# ST_LINK_V2-1.net
KiCad netlist of a schematic drawn in Altium Designer
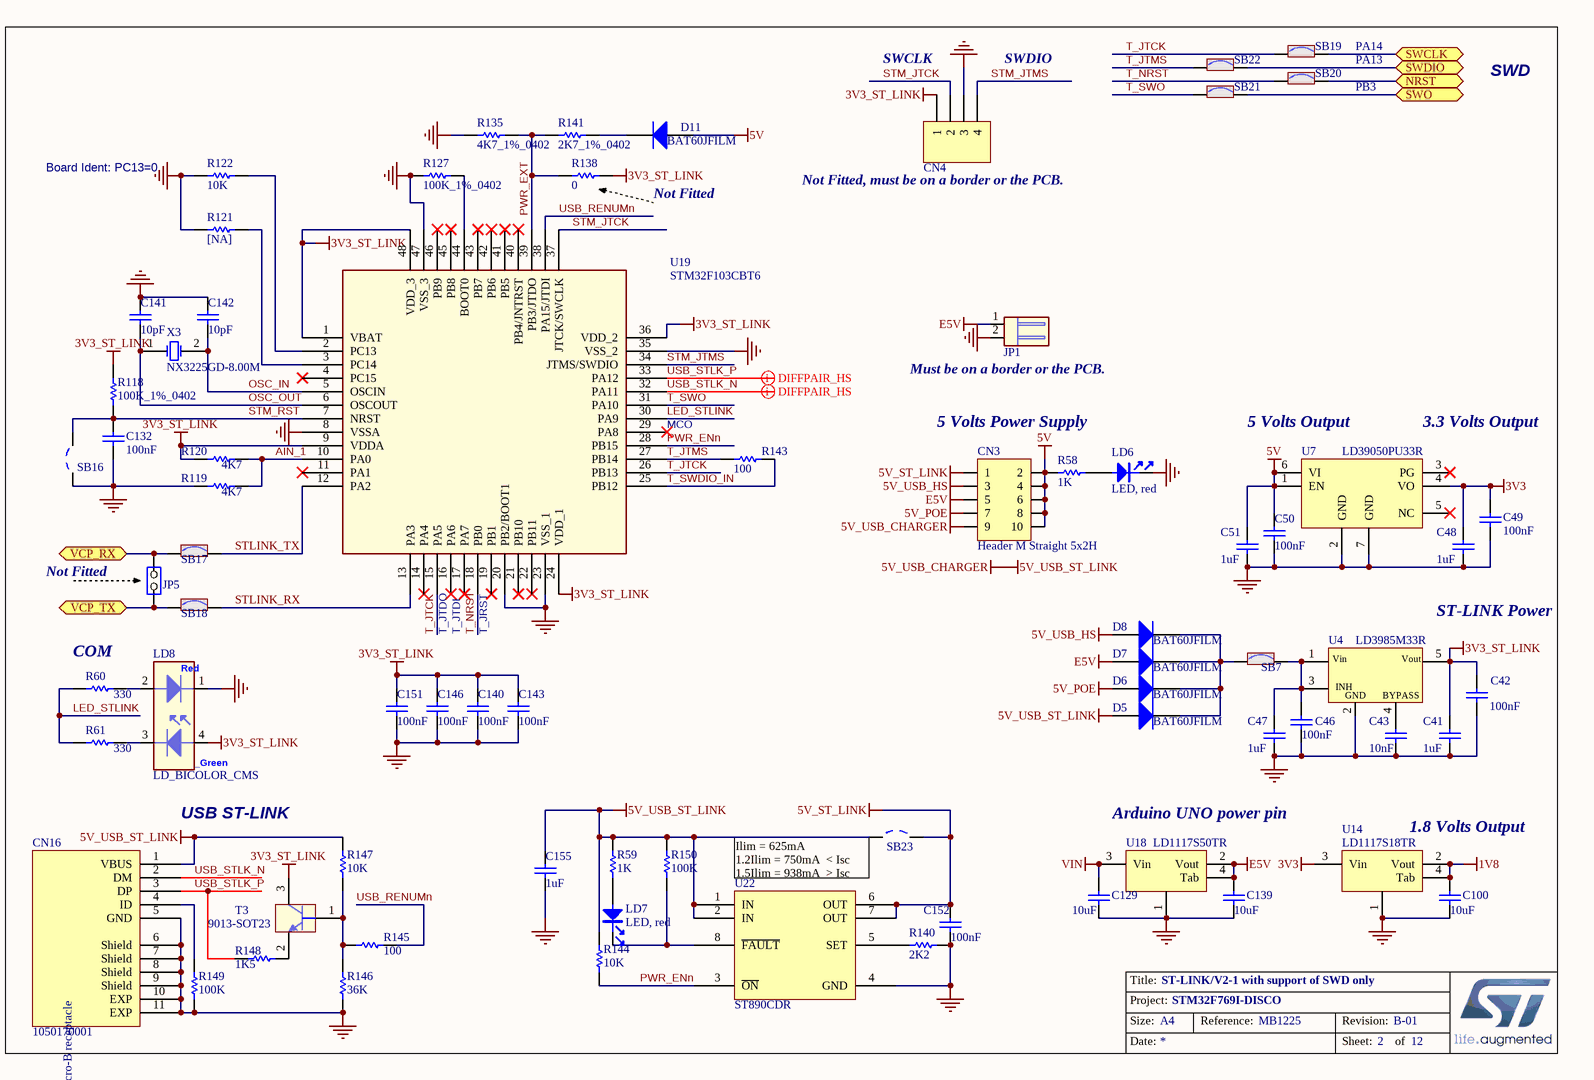
[diagram p0: ST_LINK_V2-1.SCHDOC]

(export (version "E")
  (design (tool "Eeschema 10.0.6"))
  (components
    (comp (ref "C41")
      (value "1uF")
      (footprint "0603C")
      (description "Capacitor,1uF,16V,X5R,10%,0603,YAGEO")
      (libsource (lib "MCD_TOOLS") (part "Cap_1uF_X5R_10%_0603"))
    )
    (comp (ref "C42")
      (value "100nF")
      (footprint "0402C")
      (description "Capacitor,100nF,16V,X7R,10%,0402,YAGEO")
      (libsource (lib "MCD_TOOLS") (part "Cap_100nF_X7R_10%_0402"))
    )
    (comp (ref "C43")
      (value "10nF")
      (footprint "0603C")
      (description "Capacitor,10nF,50V,X7R,10%,0603,YAGEO")
      (libsource (lib "MCD_TOOLS") (part "Cap_10nF_X7R_10%_0603"))
    )
    (comp (ref "C46")
      (value "100nF")
      (footprint "0402C")
      (description "Capacitor,100nF,16V,X7R,10%,0402,YAGEO")
      (libsource (lib "MCD_TOOLS") (part "Cap_100nF_X7R_10%_0402"))
    )
    (comp (ref "C47")
      (value "1uF")
      (footprint "0603C")
      (description "Capacitor,1uF,16V,X5R,10%,0603,YAGEO")
      (libsource (lib "MCD_TOOLS") (part "Cap_1uF_X5R_10%_0603"))
    )
    (comp (ref "C48")
      (value "1uF")
      (footprint "0603C")
      (description "Capacitor,1uF,16V,X5R,10%,0603,YAGEO")
      (libsource (lib "MCD_TOOLS") (part "Cap_1uF_X5R_10%_0603"))
    )
    (comp (ref "C49")
      (value "100nF")
      (footprint "0402C")
      (description "Capacitor,100nF,16V,X7R,10%,0402,YAGEO")
      (libsource (lib "MCD_TOOLS") (part "Cap_100nF_X7R_10%_0402"))
    )
    (comp (ref "C50")
      (value "100nF")
      (footprint "0402C")
      (description "Capacitor,100nF,16V,X7R,10%,0402,YAGEO")
      (libsource (lib "MCD_TOOLS") (part "Cap_100nF_X7R_10%_0402"))
    )
    (comp (ref "C51")
      (value "1uF")
      (footprint "0603C")
      (description "Capacitor,1uF,16V,X5R,10%,0603,YAGEO")
      (libsource (lib "MCD_TOOLS") (part "Cap_1uF_X5R_10%_0603"))
    )
    (comp (ref "C100")
      (value "10uF")
      (footprint "0603C")
      (description "Capacitor,10uF,6.3V,X5R,10%,0603,YAGEO")
      (libsource (lib "MCD_TOOLS") (part "Cap_10uF_X5R_10%_0603"))
    )
    (comp (ref "C129")
      (value "10uF")
      (footprint "0805C")
      (description "Capacitor,10uF,25V,X5R,10%,0805,YAGEO")
      (libsource (lib "MCD_TOOLS") (part "Cap_10uF_X5R_10%_0805"))
    )
    (comp (ref "C132")
      (value "100nF")
      (footprint "0402C")
      (description "Capacitor,100nF,16V,X7R,10%,0402,YAGEO")
      (libsource (lib "MCD_TOOLS") (part "Cap_100nF_X7R_10%_0402"))
    )
    (comp (ref "C139")
      (value "10uF")
      (footprint "0805C")
      (description "Capacitor,10uF,25V,X5R,10%,0805,YAGEO")
      (libsource (lib "MCD_TOOLS") (part "Cap_10uF_X5R_10%_0805"))
    )
    (comp (ref "C140")
      (value "100nF")
      (footprint "0402C")
      (description "Capacitor,100nF,16V,X7R,10%,0402,YAGEO")
      (libsource (lib "MCD_TOOLS") (part "Cap_100nF_X7R_10%_0402"))
    )
    (comp (ref "C141")
      (value "10pF")
      (footprint "0402C")
      (description "Capacitor,10pF,50V,NPO,5%,0402,YAGEO")
      (libsource (lib "MCD_TOOLS") (part "Cap_10pF_NPO_5%_0402"))
    )
    (comp (ref "C142")
      (value "10pF")
      (footprint "0402C")
      (description "Capacitor,10pF,50V,NPO,5%,0402,YAGEO")
      (libsource (lib "MCD_TOOLS") (part "Cap_10pF_NPO_5%_0402"))
    )
    (comp (ref "C143")
      (value "100nF")
      (footprint "0402C")
      (description "Capacitor,100nF,16V,X7R,10%,0402,YAGEO")
      (libsource (lib "MCD_TOOLS") (part "Cap_100nF_X7R_10%_0402"))
    )
    (comp (ref "C146")
      (value "100nF")
      (footprint "0402C")
      (description "Capacitor,100nF,16V,X7R,10%,0402,YAGEO")
      (libsource (lib "MCD_TOOLS") (part "Cap_100nF_X7R_10%_0402"))
    )
    (comp (ref "C151")
      (value "100nF")
      (footprint "0402C")
      (description "Capacitor,100nF,16V,X7R,10%,0402,YAGEO")
      (libsource (lib "MCD_TOOLS") (part "Cap_100nF_X7R_10%_0402"))
    )
    (comp (ref "C152")
      (value "100nF")
      (footprint "0402C")
      (description "Capacitor,100nF,16V,X7R,10%,0402,YAGEO")
      (libsource (lib "MCD_TOOLS") (part "Cap_100nF_X7R_10%_0402"))
    )
    (comp (ref "C155")
      (value "1uF")
      (footprint "0603C")
      (description "Capacitor,1uF,16V,X5R,10%,0603,YAGEO")
      (libsource (lib "MCD_TOOLS_CAPACITOR") (part "Cap_1uF_X5R_10%_0603"))
    )
    (comp (ref "CN3")
      (value "Header M Straight 5x2H")
      (footprint "HDR_2X5_2R54")
      (description "Header Male, 5-Pin, Dual row, Straight, AMD")
      (libsource (lib "MCD_TOOLS_CONNECTOR") (part "Header 5X2M"))
    )
    (comp (ref "CN4")
      (value "Header 4")
      (footprint "HDR_1X4_2R54")
      (description "Header, 4-Pin")
      (fields (field (name "PUBLISHER") "Altium Limited"))
      (libsource (lib "MCD_TOOLS_CONNECTOR") (part "Header 4"))
    )
    (comp (ref "CN16")
      (value "1050170001")
      (footprint "MICRO_USB_B_105017")
      (description "USB-MICRO-B, 1050170001, SMT, MOLEX")
      (libsource (lib "MCD_TOOLS_CONNECTOR") (part "1050170001"))
    )
    (comp (ref "D5")
      (value "BAT60JFILM")
      (footprint "SOD-323")
      (libsource (lib "MCD_TOOLS_MISCELLANEOUS") (part "BAT60JFILM"))
    )
    (comp (ref "D6")
      (value "BAT60JFILM")
      (footprint "SOD-323")
      (libsource (lib "MCD_TOOLS_MISCELLANEOUS") (part "BAT60JFILM"))
    )
    (comp (ref "D7")
      (value "BAT60JFILM")
      (footprint "SOD-323")
      (libsource (lib "MCD_TOOLS_MISCELLANEOUS") (part "BAT60JFILM"))
    )
    (comp (ref "D8")
      (value "BAT60JFILM")
      (footprint "SOD-323")
      (libsource (lib "MCD_TOOLS_MISCELLANEOUS") (part "BAT60JFILM"))
    )
    (comp (ref "D11")
      (value "BAT60JFILM")
      (footprint "SOD-323")
      (libsource (lib "MCD_TOOLS_MISCELLANEOUS") (part "BAT60JFILM"))
    )
    (comp (ref "JP1")
      (value "WF25402-06421")
      (footprint "HDR_1X2_2R54_RA_11R35")
      (description "Header, 2-Pins, Single row, Right Angle, 2.54 mm pitch, DIP")
      (libsource (lib "MCD_TOOLS_CONNECTOR") (part "JP2_RA"))
    )
    (comp (ref "JP5") (value "JP2") (footprint "SIP2") (libsource (lib "MCD_TOOLS_CONNECTOR") (part "JP2")))
    (comp (ref "LD6")
      (value "LED, red")
      (footprint "0603D")
      (description "LED,red,0603,19-213-R6C-AP1Q2B/3T,everlight")
      (libsource (lib "MCD_TOOLS") (part "LED_red"))
    )
    (comp (ref "LD7")
      (value "LED, red")
      (footprint "0603D")
      (description "LED,red,0603,19-213-R6C-AP1Q2B/3T,everlight")
      (libsource (lib "MCD_TOOLS") (part "LED_red"))
    )
    (comp (ref "LD8")
      (value "LD_BICOLOR_CMS")
      (footprint "LED2_3528")
      (description "Bicolor Led")
      (libsource (lib "MCD_TOOLS_MISCELLANEOUS") (part "LD_BICOLOR_CMS"))
    )
    (comp (ref "R58")
      (value "1K")
      (footprint "0402R")
      (description "Resistor,1K,0402,1%,YAGEO")
      (libsource (lib "MCD_TOOLS") (part "Res_1K_1%_0402"))
    )
    (comp (ref "R59")
      (value "1K")
      (footprint "0402R")
      (description "Resistor,1K,0402,1%,YAGEO")
      (libsource (lib "MCD_TOOLS") (part "Res_1K_1%_0402"))
    )
    (comp (ref "R60")
      (value "330")
      (footprint "0402R")
      (description "Resistor,330,0402,1%,YAGEO")
      (libsource (lib "MCD_TOOLS") (part "Res_330_1%_0402"))
    )
    (comp (ref "R61")
      (value "330")
      (footprint "0402R")
      (description "Resistor,330,0402,1%,YAGEO")
      (libsource (lib "MCD_TOOLS") (part "Res_330_1%_0402"))
    )
    (comp (ref "R118")
      (value "100K_1%_0402")
      (footprint "0402R")
      (description "Resistor,100K,0402,1%,YAGEO")
      (libsource (lib "MCD_TOOLS_RESISTOR") (part "Res_100K_1%_0402"))
    )
    (comp (ref "R119")
      (value "4K7")
      (footprint "0402R")
      (description "Resistor,4K7,0402,1%,YAGEO")
      (libsource (lib "MCD_TOOLS_RESISTOR") (part "Res_4K7_1%_0402"))
    )
    (comp (ref "R120")
      (value "4K7")
      (footprint "0402R")
      (description "Resistor,4K7,0402,1%,YAGEO")
      (libsource (lib "MCD_TOOLS_RESISTOR") (part "Res_4K7_1%_0402"))
    )
    (comp (ref "R121")
      (value "[NA]")
      (footprint "0402R")
      (description "Resistor,[NA],0402")
      (libsource (lib "MCD_TOOLS") (part "Res_NA_0402"))
    )
    (comp (ref "R122")
      (value "10K")
      (footprint "0402R")
      (description "Resistor,10K,0402,1%,YAGEO")
      (libsource (lib "MCD_TOOLS") (part "Res_10K_1%_0402"))
    )
    (comp (ref "R127")
      (value "100K_1%_0402")
      (footprint "0402R")
      (description "Resistor,100K,0402,1%,YAGEO")
      (libsource (lib "MCD_TOOLS_RESISTOR") (part "Res_100K_1%_0402"))
    )
    (comp (ref "R135")
      (value "4K7_1%_0402")
      (footprint "0402R")
      (description "Resistor,4K7,0402,1%,YAGEO")
      (libsource (lib "MCD_TOOLS_RESISTOR") (part "Res_4K7_1%_0402"))
    )
    (comp (ref "R138")
      (value "0")
      (footprint "0402R")
      (description "Resistor,0,0402,5%,YAGEO")
      (libsource (lib "MCD_TOOLS") (part "Res_0_5%_0402"))
    )
    (comp (ref "R140")
      (value "2K2")
      (footprint "0402R")
      (description "Resistor,2K2,0402,1%,YAGEO")
      (libsource (lib "MCD_TOOLS_RESISTOR") (part "Res_2K2_1%_0402"))
    )
    (comp (ref "R141")
      (value "2K7_1%_0402")
      (footprint "0402R")
      (description "Resistor,2K7,0402,1%,YAGEO")
      (libsource (lib "MCD_TOOLS_RESISTOR") (part "Res_2K7_1%_0402"))
    )
    (comp (ref "R143")
      (value "100")
      (footprint "0402R")
      (description "Resistor,100,0402,1%,YAGEO")
      (libsource (lib "MCD_TOOLS") (part "Res_100_1%_0402"))
    )
    (comp (ref "R144")
      (value "10K")
      (footprint "0402R")
      (description "Resistor,10K,0402,1%,YAGEO")
      (libsource (lib "MCD_TOOLS") (part "Res_10K_1%_0402"))
    )
    (comp (ref "R145")
      (value "100")
      (footprint "0402R")
      (description "Resistor,100,0402,1%,YAGEO")
      (libsource (lib "MCD_TOOLS") (part "Res_100_1%_0402"))
    )
    (comp (ref "R146")
      (value "36K")
      (footprint "0402R")
      (description "Resistor,36K,0402,1%,YAGEO")
      (libsource (lib "MCD_TOOLS") (part "Res_36K_1%_0402"))
    )
    (comp (ref "R147")
      (value "10K")
      (footprint "0402R")
      (description "Resistor,10K,0402,1%,YAGEO")
      (libsource (lib "MCD_TOOLS") (part "Res_10K_1%_0402"))
    )
    (comp (ref "R148")
      (value "1K5")
      (footprint "0402R")
      (description "Resistor,1K5,0402,1%,YAGEO")
      (libsource (lib "MCD_TOOLS") (part "Res_1K5_1%_0402"))
    )
    (comp (ref "R149")
      (value "100K")
      (footprint "0402R")
      (description "Resistor,100K,0402,1%,YAGEO")
      (libsource (lib "MCD_TOOLS_RESISTOR") (part "Res_100K_1%_0402"))
    )
    (comp (ref "R150")
      (value "100K")
      (footprint "0402R")
      (description "Resistor,100K,0402,1%,YAGEO")
      (libsource (lib "MCD_TOOLS_RESISTOR") (part "Res_100K_1%_0402"))
    )
    (comp (ref "SB7")
      (value "Solder Bridge ON")
      (footprint "JP2_SMD")
      (libsource (lib "MCD_TOOLS") (part "SB_ON"))
    )
    (comp (ref "SB16")
      (value "Solder Bridge OFF")
      (footprint "JP2_SMD")
      (libsource (lib "MCD_TOOLS") (part "SB_OFF"))
    )
    (comp (ref "SB17")
      (value "Solder Bridge ON")
      (footprint "JP2_SMD")
      (libsource (lib "MCD_TOOLS") (part "SB_ON"))
    )
    (comp (ref "SB18")
      (value "Solder Bridge ON")
      (footprint "JP2_SMD")
      (libsource (lib "MCD_TOOLS") (part "SB_ON"))
    )
    (comp (ref "SB19")
      (value "Solder Bridge ON")
      (footprint "JP2_SMD")
      (libsource (lib "MCD_TOOLS") (part "SB_ON"))
    )
    (comp (ref "SB20")
      (value "Solder Bridge ON")
      (footprint "JP2_SMD")
      (libsource (lib "MCD_TOOLS") (part "SB_ON"))
    )
    (comp (ref "SB21")
      (value "Solder Bridge ON")
      (footprint "JP2_SMD")
      (libsource (lib "MCD_TOOLS") (part "SB_ON"))
    )
    (comp (ref "SB22")
      (value "Solder Bridge ON")
      (footprint "JP2_SMD")
      (libsource (lib "MCD_TOOLS") (part "SB_ON"))
    )
    (comp (ref "SB23")
      (value "Solder Bridge OFF")
      (footprint "JP2_SMD")
      (libsource (lib "MCD_TOOLS") (part "SB_OFF"))
    )
    (comp (ref "T3")
      (value "9013-SOT23")
      (footprint "SOT-23")
      (description "NPN Bipolar Transistor, SOT-23 Footprint")
      (libsource (lib "MCD_TOOLS_MISCELLANEOUS") (part "9013-SOT23"))
    )
    (comp (ref "U4")
      (value "LD3985M33R")
      (footprint "SOT-23-5L")
      (description "Ultra low drop-low noise BiCMOS voltage, regulators low ESR capacitors compatible")
      (libsource (lib "MCD_TOOLS_MISCELLANEOUS") (part "LD3985M33R"))
    )
    (comp (ref "U7")
      (value "LD39050PU33R")
      (footprint "DFN6_0R95_3X3")
      (description "Ultra low drop-low , 500 mA low quiescent current")
      (libsource (lib "MCD_TOOLS_MISCELLANEOUS") (part "LD39050P"))
    )
    (comp (ref "U14")
      (value "LD1117S18TR")
      (footprint "SOT-223")
      (description "LOW DROP FIXED AND ADJUSTABLE POSITIVE VOLTAGE REGULATORS (1.8 Volts)")
      (libsource (lib "MCD_TOOLS") (part "LD1117S18TR"))
    )
    (comp (ref "U18")
      (value "LD1117S50TR")
      (footprint "SOT-223")
      (description "IC REG LDO 5V 0.8A SOT223")
      (libsource (lib "MCD_TOOLS") (part "LD1117S50TR"))
    )
    (comp (ref "U19")
      (value "STM32F103CBT6")
      (footprint "LQFP48_0R5_9X9")
      (description "Medium-density performance line ARM-based 32-bit MCU with 128KB Flash")
      (libsource (lib "MCD_TOOLS_MCU") (part "STM32F103CBT6"))
    )
    (comp (ref "U22")
      (value "ST890CDR")
      (footprint "SOIC8_1R27_4R9X6")
      (description "1.2 A current limited high-side power switch with thermal shutdown")
      (libsource (lib "MCD_TOOLS_MISCELLANEOUS") (part "ST890CDR"))
    )
    (comp (ref "X3")
      (value "NX3225GD-8.00M")
      (footprint "XTAL_2SM_3R2X2R5_H1")
      (description "Crystal 8Mhz, 8pF, -+50PPM, SMD")
      (libsource (lib "MCD_TOOLS_MISCELLANEOUS") (part "XTAL_8M_NX3225GD"))
    )
  )
  (nets
    (net (code "1") (name "/AIN_1") (class "Default")
      (node (ref "R119") (pin "2") (pinfunction "2_2") (pintype "passive"))
      (node (ref "R120") (pin "2") (pinfunction "2_2") (pintype "passive"))
      (node (ref "U19") (pin "10") (pinfunction "PA0_10") (pintype "passive"))
    )
    (net (code "2") (name "/LED_STLINK") (class "Default")
      (node (ref "R60") (pin "1") (pinfunction "1_1") (pintype "passive"))
      (node (ref "R61") (pin "1") (pinfunction "1_1") (pintype "passive"))
      (node (ref "U19") (pin "30") (pinfunction "PA9_30") (pintype "passive"))
    )
    (net (code "3") (name "/NRST") (class "Default")
      (node (ref "SB20") (pin "2") (pinfunction "2_2") (pintype "passive"))
    )
    (net (code "4") (name "/OSC_IN") (class "Default")
      (node (ref "C142") (pin "2") (pinfunction "2_2") (pintype "passive"))
      (node (ref "U19") (pin "5") (pinfunction "OSCIN_5") (pintype "passive"))
      (node (ref "X3") (pin "2") (pinfunction "OSC2_2") (pintype "passive"))
    )
    (net (code "5") (name "/OSC_OUT") (class "Default")
      (node (ref "C141") (pin "2") (pinfunction "2_2") (pintype "passive"))
      (node (ref "U19") (pin "6") (pinfunction "OSCOUT_6") (pintype "passive"))
      (node (ref "X3") (pin "1") (pinfunction "OSC1_1") (pintype "passive"))
    )
    (net (code "6") (name "/PWR_ENn") (class "Default")
      (node (ref "R144") (pin "1") (pinfunction "1_1") (pintype "passive"))
      (node (ref "U19") (pin "28") (pinfunction "PB15_28") (pintype "passive"))
      (node (ref "U22") (pin "3") (pinfunction "~{ON}_3") (pintype "passive"))
    )
    (net (code "7") (name "/PWR_EXT") (class "Default")
      (node (ref "R135") (pin "2") (pinfunction "2_2") (pintype "passive"))
      (node (ref "R138") (pin "1") (pinfunction "1_1") (pintype "passive"))
      (node (ref "R141") (pin "1") (pinfunction "1_1") (pintype "passive"))
      (node (ref "U19") (pin "39") (pinfunction "PB3/JTDO_39") (pintype "passive"))
    )
    (net (code "8") (name "/STLINK_RX") (class "Default")
      (node (ref "SB18") (pin "2") (pinfunction "2_2") (pintype "passive"))
      (node (ref "U19") (pin "13") (pinfunction "PA3_13") (pintype "passive"))
    )
    (net (code "9") (name "/STLINK_TX") (class "Default")
      (node (ref "SB17") (pin "2") (pinfunction "2_2") (pintype "passive"))
      (node (ref "U19") (pin "12") (pinfunction "PA2_12") (pintype "passive"))
    )
    (net (code "10") (name "/STM_JTCK") (class "Default")
      (node (ref "CN4") (pin "2") (pinfunction "2_2") (pintype "passive"))
      (node (ref "U19") (pin "37") (pinfunction "JTCK/SWCLK_37") (pintype "passive"))
    )
    (net (code "11") (name "/STM_JTMS") (class "Default")
      (node (ref "CN4") (pin "4") (pinfunction "4_4") (pintype "passive"))
      (node (ref "U19") (pin "34") (pinfunction "JTMS/SWDIO_34") (pintype "passive"))
    )
    (net (code "12") (name "/STM_RST") (class "Default")
      (node (ref "C132") (pin "2") (pinfunction "2_2") (pintype "passive"))
      (node (ref "R118") (pin "1") (pinfunction "1_1") (pintype "passive"))
      (node (ref "SB16") (pin "2") (pinfunction "2_2") (pintype "passive"))
      (node (ref "U19") (pin "7") (pinfunction "NRST_7") (pintype "passive"))
    )
    (net (code "13") (name "/SWCLK") (class "Default")
      (node (ref "SB19") (pin "2") (pinfunction "2_2") (pintype "passive"))
    )
    (net (code "14") (name "/SWDIO") (class "Default")
      (node (ref "SB22") (pin "2") (pinfunction "2_2") (pintype "passive"))
    )
    (net (code "15") (name "/SWO") (class "Default")
      (node (ref "SB21") (pin "2") (pinfunction "2_2") (pintype "passive"))
    )
    (net (code "16") (name "/T_JTCK") (class "Default")
      (node (ref "SB19") (pin "1") (pinfunction "1_1") (pintype "passive"))
      (node (ref "U19") (pin "15") (pinfunction "PA5_15") (pintype "passive"))
      (node (ref "U19") (pin "26") (pinfunction "PB13_26") (pintype "passive"))
    )
    (net (code "17") (name "/T_JTMS") (class "Default")
      (node (ref "R143") (pin "1") (pinfunction "1_1") (pintype "passive"))
      (node (ref "SB22") (pin "1") (pinfunction "1_1") (pintype "passive"))
      (node (ref "U19") (pin "27") (pinfunction "PB14_27") (pintype "passive"))
    )
    (net (code "18") (name "/T_NRST") (class "Default")
      (node (ref "SB20") (pin "1") (pinfunction "1_1") (pintype "passive"))
      (node (ref "U19") (pin "18") (pinfunction "PB0_18") (pintype "passive"))
    )
    (net (code "19") (name "/T_SWDIO_IN") (class "Default")
      (node (ref "R143") (pin "2") (pinfunction "2_2") (pintype "passive"))
      (node (ref "U19") (pin "25") (pinfunction "PB12_25") (pintype "passive"))
    )
    (net (code "20") (name "/T_SWO") (class "Default")
      (node (ref "SB21") (pin "1") (pinfunction "1_1") (pintype "passive"))
      (node (ref "U19") (pin "31") (pinfunction "PA10_31") (pintype "passive"))
    )
    (net (code "21") (name "/USB_RENUMn") (class "Default")
      (node (ref "R145") (pin "2") (pinfunction "2_2") (pintype "passive"))
      (node (ref "U19") (pin "38") (pinfunction "PA15/JTDI_38") (pintype "passive"))
    )
    (net (code "22") (name "/USB_STLK_N") (class "Default")
      (node (ref "CN16") (pin "2") (pinfunction "DM_2") (pintype "passive"))
      (node (ref "U19") (pin "32") (pinfunction "PA11_32") (pintype "passive"))
    )
    (net (code "23") (name "/USB_STLK_P") (class "Default")
      (node (ref "CN16") (pin "3") (pinfunction "DP_3") (pintype "passive"))
      (node (ref "R148") (pin "1") (pinfunction "1_1") (pintype "passive"))
      (node (ref "U19") (pin "33") (pinfunction "PA12_33") (pintype "passive"))
    )
    (net (code "24") (name "/VCP_RX") (class "Default")
      (node (ref "JP5") (pin "2") (pinfunction "NO_2") (pintype "passive"))
      (node (ref "SB17") (pin "1") (pinfunction "1_1") (pintype "passive"))
    )
    (net (code "25") (name "/VCP_TX") (class "Default")
      (node (ref "JP5") (pin "1") (pinfunction "COMMON_1") (pintype "passive"))
      (node (ref "SB18") (pin "1") (pinfunction "1_1") (pintype "passive"))
    )
    (net (code "26") (name "1V8") (class "Default")
      (node (ref "C100") (pin "2") (pinfunction "2_2") (pintype "passive"))
      (node (ref "U14") (pin "2") (pinfunction "Vout_2") (pintype "passive"))
      (node (ref "U14") (pin "4") (pinfunction "Tab_4") (pintype "passive"))
    )
    (net (code "27") (name "3V3") (class "Default")
      (node (ref "C48") (pin "2") (pinfunction "2_2") (pintype "passive"))
      (node (ref "C49") (pin "2") (pinfunction "2_2") (pintype "passive"))
      (node (ref "U14") (pin "3") (pinfunction "Vin_3") (pintype "passive"))
      (node (ref "U7") (pin "4") (pinfunction "VO_4") (pintype "passive"))
    )
    (net (code "28") (name "3V3_ST_LINK") (class "Default")
      (node (ref "C140") (pin "1") (pinfunction "1_1") (pintype "passive"))
      (node (ref "C143") (pin "2") (pinfunction "2_2") (pintype "passive"))
      (node (ref "C146") (pin "2") (pinfunction "2_2") (pintype "passive"))
      (node (ref "C151") (pin "2") (pinfunction "2_2") (pintype "passive"))
      (node (ref "C41") (pin "1") (pinfunction "1_1") (pintype "passive"))
      (node (ref "C42") (pin "2") (pinfunction "2_2") (pintype "passive"))
      (node (ref "CN4") (pin "1") (pinfunction "1_1") (pintype "passive"))
      (node (ref "LD8") (pin "4") (pinfunction "4_4") (pintype "passive"))
      (node (ref "R118") (pin "2") (pinfunction "2_2") (pintype "passive"))
      (node (ref "R120") (pin "1") (pinfunction "1_1") (pintype "passive"))
      (node (ref "R138") (pin "2") (pinfunction "2_2") (pintype "passive"))
      (node (ref "T3") (pin "3") (pinfunction "C_3") (pintype "passive"))
      (node (ref "U19") (pin "1") (pinfunction "VBAT_1") (pintype "passive"))
      (node (ref "U19") (pin "24") (pinfunction "VDD_1_24") (pintype "passive"))
      (node (ref "U19") (pin "36") (pinfunction "VDD_2_36") (pintype "passive"))
      (node (ref "U19") (pin "48") (pinfunction "VDD_3_48") (pintype "passive"))
      (node (ref "U19") (pin "9") (pinfunction "VDDA_9") (pintype "passive"))
      (node (ref "U4") (pin "5") (pinfunction "Vout_5") (pintype "passive"))
    )
    (net (code "29") (name "5V") (class "Default")
      (node (ref "C50") (pin "2") (pinfunction "2_2") (pintype "passive"))
      (node (ref "C51") (pin "2") (pinfunction "2_2") (pintype "passive"))
      (node (ref "CN3") (pin "10") (pinfunction "10_10") (pintype "passive"))
      (node (ref "CN3") (pin "2") (pinfunction "2_2") (pintype "passive"))
      (node (ref "CN3") (pin "4") (pinfunction "4_4") (pintype "passive"))
      (node (ref "CN3") (pin "6") (pinfunction "6_6") (pintype "passive"))
      (node (ref "CN3") (pin "8") (pinfunction "8_8") (pintype "passive"))
      (node (ref "D11") (pin "1") (pinfunction "A_1") (pintype "passive"))
      (node (ref "R58") (pin "1") (pinfunction "1_1") (pintype "passive"))
      (node (ref "U7") (pin "1") (pinfunction "EN_1") (pintype "passive"))
      (node (ref "U7") (pin "6") (pinfunction "VI_6") (pintype "passive"))
    )
    (net (code "30") (name "5V_POE") (class "Default")
      (node (ref "CN3") (pin "7") (pinfunction "7_7") (pintype "passive"))
      (node (ref "D6") (pin "1") (pinfunction "A_1") (pintype "passive"))
    )
    (net (code "31") (name "5V_ST_LINK") (class "Default")
      (node (ref "C152") (pin "2") (pinfunction "2_2") (pintype "passive"))
      (node (ref "CN3") (pin "1") (pinfunction "1_1") (pintype "passive"))
      (node (ref "SB23") (pin "2") (pinfunction "2_2") (pintype "passive"))
      (node (ref "U22") (pin "6") (pinfunction "OUT_6") (pintype "passive"))
      (node (ref "U22") (pin "7") (pinfunction "OUT_7") (pintype "passive"))
    )
    (net (code "32") (name "5V_USB_CHARGER") (class "Default")
      (node (ref "C155") (pin "2") (pinfunction "2_2") (pintype "passive"))
      (node (ref "CN16") (pin "1") (pinfunction "VBUS_1") (pintype "passive"))
      (node (ref "CN3") (pin "9") (pinfunction "9_9") (pintype "passive"))
      (node (ref "D5") (pin "1") (pinfunction "A_1") (pintype "passive"))
      (node (ref "R144") (pin "2") (pinfunction "2_2") (pintype "passive"))
      (node (ref "R147") (pin "2") (pinfunction "2_2") (pintype "passive"))
      (node (ref "R150") (pin "2") (pinfunction "2_2") (pintype "passive"))
      (node (ref "R59") (pin "2") (pinfunction "2_2") (pintype "passive"))
      (node (ref "SB23") (pin "1") (pinfunction "1_1") (pintype "passive"))
      (node (ref "U22") (pin "1") (pinfunction "IN_1") (pintype "passive"))
      (node (ref "U22") (pin "2") (pinfunction "IN_2") (pintype "passive"))
    )
    (net (code "33") (name "5V_USB_HS") (class "Default")
      (node (ref "CN3") (pin "3") (pinfunction "3_3") (pintype "passive"))
      (node (ref "D8") (pin "1") (pinfunction "A_1") (pintype "passive"))
    )
    (net (code "34") (name "E5V") (class "Default")
      (node (ref "C139") (pin "2") (pinfunction "2_2") (pintype "passive"))
      (node (ref "CN3") (pin "5") (pinfunction "5_5") (pintype "passive"))
      (node (ref "D7") (pin "1") (pinfunction "A_1") (pintype "passive"))
      (node (ref "JP1") (pin "1") (pinfunction "1_1") (pintype "passive"))
      (node (ref "U18") (pin "2") (pinfunction "Vout_2") (pintype "passive"))
      (node (ref "U18") (pin "4") (pinfunction "Tab_4") (pintype "passive"))
    )
    (net (code "35") (name "GND") (class "Default")
      (node (ref "C100") (pin "1") (pinfunction "1_1") (pintype "passive"))
      (node (ref "C129") (pin "1") (pinfunction "1_1") (pintype "passive"))
      (node (ref "C132") (pin "1") (pinfunction "1_1") (pintype "passive"))
      (node (ref "C139") (pin "1") (pinfunction "1_1") (pintype "passive"))
      (node (ref "C140") (pin "2") (pinfunction "2_2") (pintype "passive"))
      (node (ref "C141") (pin "1") (pinfunction "1_1") (pintype "passive"))
      (node (ref "C142") (pin "1") (pinfunction "1_1") (pintype "passive"))
      (node (ref "C143") (pin "1") (pinfunction "1_1") (pintype "passive"))
      (node (ref "C146") (pin "1") (pinfunction "1_1") (pintype "passive"))
      (node (ref "C151") (pin "1") (pinfunction "1_1") (pintype "passive"))
      (node (ref "C152") (pin "1") (pinfunction "1_1") (pintype "passive"))
      (node (ref "C155") (pin "1") (pinfunction "1_1") (pintype "passive"))
      (node (ref "C41") (pin "2") (pinfunction "2_2") (pintype "passive"))
      (node (ref "C42") (pin "1") (pinfunction "1_1") (pintype "passive"))
      (node (ref "C43") (pin "1") (pinfunction "1_1") (pintype "passive"))
      (node (ref "C46") (pin "1") (pinfunction "1_1") (pintype "passive"))
      (node (ref "C47") (pin "1") (pinfunction "1_1") (pintype "passive"))
      (node (ref "C48") (pin "1") (pinfunction "1_1") (pintype "passive"))
      (node (ref "C49") (pin "1") (pinfunction "1_1") (pintype "passive"))
      (node (ref "C50") (pin "1") (pinfunction "1_1") (pintype "passive"))
      (node (ref "C51") (pin "1") (pinfunction "1_1") (pintype "passive"))
      (node (ref "CN16") (pin "10") (pinfunction "EXP_10") (pintype "passive"))
      (node (ref "CN16") (pin "11") (pinfunction "EXP_11") (pintype "passive"))
      (node (ref "CN16") (pin "5") (pinfunction "GND_5") (pintype "passive"))
      (node (ref "CN16") (pin "6") (pinfunction "Shield_6") (pintype "passive"))
      (node (ref "CN16") (pin "7") (pinfunction "Shield_7") (pintype "passive"))
      (node (ref "CN16") (pin "8") (pinfunction "Shield_8") (pintype "passive"))
      (node (ref "CN16") (pin "9") (pinfunction "Shield_9") (pintype "passive"))
      (node (ref "CN4") (pin "3") (pinfunction "3_3") (pintype "passive"))
      (node (ref "JP1") (pin "2") (pinfunction "2_2") (pintype "passive"))
      (node (ref "LD6") (pin "2") (pintype "passive"))
      (node (ref "LD8") (pin "1") (pinfunction "1_1") (pintype "passive"))
      (node (ref "R119") (pin "1") (pinfunction "1_1") (pintype "passive"))
      (node (ref "R121") (pin "1") (pinfunction "1_1") (pintype "passive"))
      (node (ref "R122") (pin "1") (pinfunction "1_1") (pintype "passive"))
      (node (ref "R127") (pin "1") (pinfunction "1_1") (pintype "passive"))
      (node (ref "R135") (pin "1") (pinfunction "1_1") (pintype "passive"))
      (node (ref "R140") (pin "2") (pinfunction "2_2") (pintype "passive"))
      (node (ref "R146") (pin "1") (pinfunction "1_1") (pintype "passive"))
      (node (ref "R149") (pin "1") (pinfunction "1_1") (pintype "passive"))
      (node (ref "SB16") (pin "1") (pinfunction "1_1") (pintype "passive"))
      (node (ref "U14") (pin "1") (pintype "passive"))
      (node (ref "U18") (pin "1") (pintype "passive"))
      (node (ref "U19") (pin "20") (pinfunction "PB2/BOOT1_20") (pintype "passive"))
      (node (ref "U19") (pin "23") (pinfunction "VSS_1_23") (pintype "passive"))
      (node (ref "U19") (pin "35") (pinfunction "VSS_2_35") (pintype "passive"))
      (node (ref "U19") (pin "47") (pinfunction "VSS_3_47") (pintype "passive"))
      (node (ref "U19") (pin "8") (pinfunction "VSSA_8") (pintype "passive"))
      (node (ref "U22") (pin "4") (pinfunction "GND_4") (pintype "passive"))
      (node (ref "U4") (pin "2") (pinfunction "GND_2") (pintype "passive"))
      (node (ref "U7") (pin "2") (pinfunction "GND_2") (pintype "passive"))
      (node (ref "U7") (pin "7") (pinfunction "GND_7") (pintype "passive"))
    )
    (net (code "36") (name "Net-(CN16-ID)") (class "Default")
      (node (ref "CN16") (pin "4") (pinfunction "ID_4") (pintype "passive"))
      (node (ref "R149") (pin "2") (pinfunction "2_2") (pintype "passive"))
    )
    (net (code "37") (name "Net-(D5-K)") (class "Default")
      (node (ref "D5") (pin "2") (pinfunction "K_2") (pintype "passive"))
      (node (ref "D6") (pin "2") (pinfunction "K_2") (pintype "passive"))
      (node (ref "D7") (pin "2") (pinfunction "K_2") (pintype "passive"))
      (node (ref "D8") (pin "2") (pinfunction "K_2") (pintype "passive"))
      (node (ref "SB7") (pin "1") (pinfunction "1_1") (pintype "passive"))
    )
    (net (code "38") (name "Net-(D11-K)") (class "Default")
      (node (ref "D11") (pin "2") (pinfunction "K_2") (pintype "passive"))
      (node (ref "R141") (pin "2") (pinfunction "2_2") (pintype "passive"))
    )
    (net (code "39") (name "Net-(LD6-Pad1)") (class "Default")
      (node (ref "LD6") (pin "1") (pintype "passive"))
      (node (ref "R58") (pin "2") (pinfunction "2_2") (pintype "passive"))
    )
    (net (code "40") (name "Net-(LD7-Pad1)") (class "Default")
      (node (ref "LD7") (pin "1") (pintype "passive"))
      (node (ref "R59") (pin "1") (pinfunction "1_1") (pintype "passive"))
    )
    (net (code "41") (name "Net-(LD8-Pad2)") (class "Default")
      (node (ref "LD8") (pin "2") (pinfunction "2_2") (pintype "passive"))
      (node (ref "R60") (pin "2") (pinfunction "2_2") (pintype "passive"))
    )
    (net (code "42") (name "Net-(LD8-Pad3)") (class "Default")
      (node (ref "LD8") (pin "3") (pinfunction "3_3") (pintype "passive"))
      (node (ref "R61") (pin "2") (pinfunction "2_2") (pintype "passive"))
    )
    (net (code "43") (name "Net-(T3-B)") (class "Default")
      (node (ref "R145") (pin "1") (pinfunction "1_1") (pintype "passive"))
      (node (ref "R146") (pin "2") (pinfunction "2_2") (pintype "passive"))
      (node (ref "R147") (pin "1") (pinfunction "1_1") (pintype "passive"))
      (node (ref "T3") (pin "1") (pinfunction "B_1") (pintype "passive"))
    )
    (net (code "44") (name "Net-(T3-E)") (class "Default")
      (node (ref "R148") (pin "2") (pinfunction "2_2") (pintype "passive"))
      (node (ref "T3") (pin "2") (pinfunction "E_2") (pintype "passive"))
    )
    (net (code "45") (name "Net-(U4-BYPASS)") (class "Default")
      (node (ref "C43") (pin "2") (pinfunction "2_2") (pintype "passive"))
      (node (ref "U4") (pin "4") (pinfunction "BYPASS_4") (pintype "passive"))
    )
    (net (code "46") (name "Net-(U4-CE)") (class "Default")
      (node (ref "C46") (pin "2") (pinfunction "2_2") (pintype "passive"))
      (node (ref "C47") (pin "2") (pinfunction "2_2") (pintype "passive"))
      (node (ref "SB7") (pin "2") (pinfunction "2_2") (pintype "passive"))
      (node (ref "U4") (pin "1") (pinfunction "Vin_1") (pintype "passive"))
      (node (ref "U4") (pin "3") (pinfunction "CE_3") (pintype "passive"))
    )
    (net (code "47") (name "Net-(U19-BOOT0)") (class "Default")
      (node (ref "R127") (pin "2") (pinfunction "2_2") (pintype "passive"))
      (node (ref "U19") (pin "44") (pinfunction "BOOT0_44") (pintype "passive"))
    )
    (net (code "48") (name "Net-(U19-PC13)") (class "Default")
      (node (ref "R122") (pin "2") (pinfunction "2_2") (pintype "passive"))
      (node (ref "U19") (pin "2") (pinfunction "PC13_2") (pintype "passive"))
    )
    (net (code "49") (name "Net-(U19-PC14)") (class "Default")
      (node (ref "R121") (pin "2") (pinfunction "2_2") (pintype "passive"))
      (node (ref "U19") (pin "3") (pinfunction "PC14_3") (pintype "passive"))
    )
    (net (code "50") (name "Net-(U22-SET)") (class "Default")
      (node (ref "R140") (pin "1") (pinfunction "1_1") (pintype "passive"))
      (node (ref "U22") (pin "5") (pinfunction "SET_5") (pintype "passive"))
    )
    (net (code "51") (name "Net-(U22-~{FAULT})") (class "Default")
      (node (ref "LD7") (pin "2") (pintype "passive"))
      (node (ref "R150") (pin "1") (pinfunction "1_1") (pintype "passive"))
      (node (ref "U22") (pin "8") (pinfunction "~{FAULT}_8") (pintype "passive"))
    )
    (net (code "52") (name "VIN") (class "Default")
      (node (ref "C129") (pin "2") (pinfunction "2_2") (pintype "passive"))
      (node (ref "U18") (pin "3") (pinfunction "Vin_3") (pintype "passive"))
    )
    (net (code "53") (name "unconnected-(U7-NC-Pad5)") (class "Default")
      (node (ref "U7") (pin "5") (pinfunction "NC_5") (pintype "passive+no_connect"))
    )
    (net (code "54") (name "unconnected-(U7-PG-Pad3)") (class "Default")
      (node (ref "U7") (pin "3") (pinfunction "PG_3") (pintype "passive+no_connect"))
    )
    (net (code "55") (name "unconnected-(U19-PA1-Pad11)") (class "Default")
      (node (ref "U19") (pin "11") (pinfunction "PA1_11") (pintype "passive+no_connect"))
    )
    (net (code "56") (name "unconnected-(U19-PA4-Pad14)") (class "Default")
      (node (ref "U19") (pin "14") (pinfunction "PA4_14") (pintype "passive+no_connect"))
    )
    (net (code "57") (name "unconnected-(U19-PA6-Pad16)") (class "Default")
      (node (ref "U19") (pin "16") (pinfunction "PA6_16") (pintype "passive+no_connect"))
    )
    (net (code "58") (name "unconnected-(U19-PA7-Pad17)") (class "Default")
      (node (ref "U19") (pin "17") (pinfunction "PA7_17") (pintype "passive+no_connect"))
    )
    (net (code "59") (name "unconnected-(U19-PA8-Pad29)") (class "Default")
      (node (ref "U19") (pin "29") (pinfunction "PA8_29") (pintype "passive+no_connect"))
    )
    (net (code "60") (name "unconnected-(U19-PB1-Pad19)") (class "Default")
      (node (ref "U19") (pin "19") (pinfunction "PB1_19") (pintype "passive+no_connect"))
    )
    (net (code "61") (name "unconnected-(U19-PB4{slash}JNTRST-Pad40)") (class "Default")
      (node (ref "U19") (pin "40") (pinfunction "PB4/JNTRST_40") (pintype "passive+no_connect"))
    )
    (net (code "62") (name "unconnected-(U19-PB5-Pad41)") (class "Default")
      (node (ref "U19") (pin "41") (pinfunction "PB5_41") (pintype "passive+no_connect"))
    )
    (net (code "63") (name "unconnected-(U19-PB6-Pad42)") (class "Default")
      (node (ref "U19") (pin "42") (pinfunction "PB6_42") (pintype "passive+no_connect"))
    )
    (net (code "64") (name "unconnected-(U19-PB7-Pad43)") (class "Default")
      (node (ref "U19") (pin "43") (pinfunction "PB7_43") (pintype "passive+no_connect"))
    )
    (net (code "65") (name "unconnected-(U19-PB8-Pad45)") (class "Default")
      (node (ref "U19") (pin "45") (pinfunction "PB8_45") (pintype "passive+no_connect"))
    )
    (net (code "66") (name "unconnected-(U19-PB9-Pad46)") (class "Default")
      (node (ref "U19") (pin "46") (pinfunction "PB9_46") (pintype "passive+no_connect"))
    )
    (net (code "67") (name "unconnected-(U19-PB10-Pad21)") (class "Default")
      (node (ref "U19") (pin "21") (pinfunction "PB10_21") (pintype "passive+no_connect"))
    )
    (net (code "68") (name "unconnected-(U19-PB11-Pad22)") (class "Default")
      (node (ref "U19") (pin "22") (pinfunction "PB11_22") (pintype "passive+no_connect"))
    )
    (net (code "69") (name "unconnected-(U19-PC15-Pad4)") (class "Default")
      (node (ref "U19") (pin "4") (pinfunction "PC15_4") (pintype "passive+no_connect"))
    )
  )
)
